# USB_HUB.net
KiCad netlist of a schematic drawn in Altium Designer
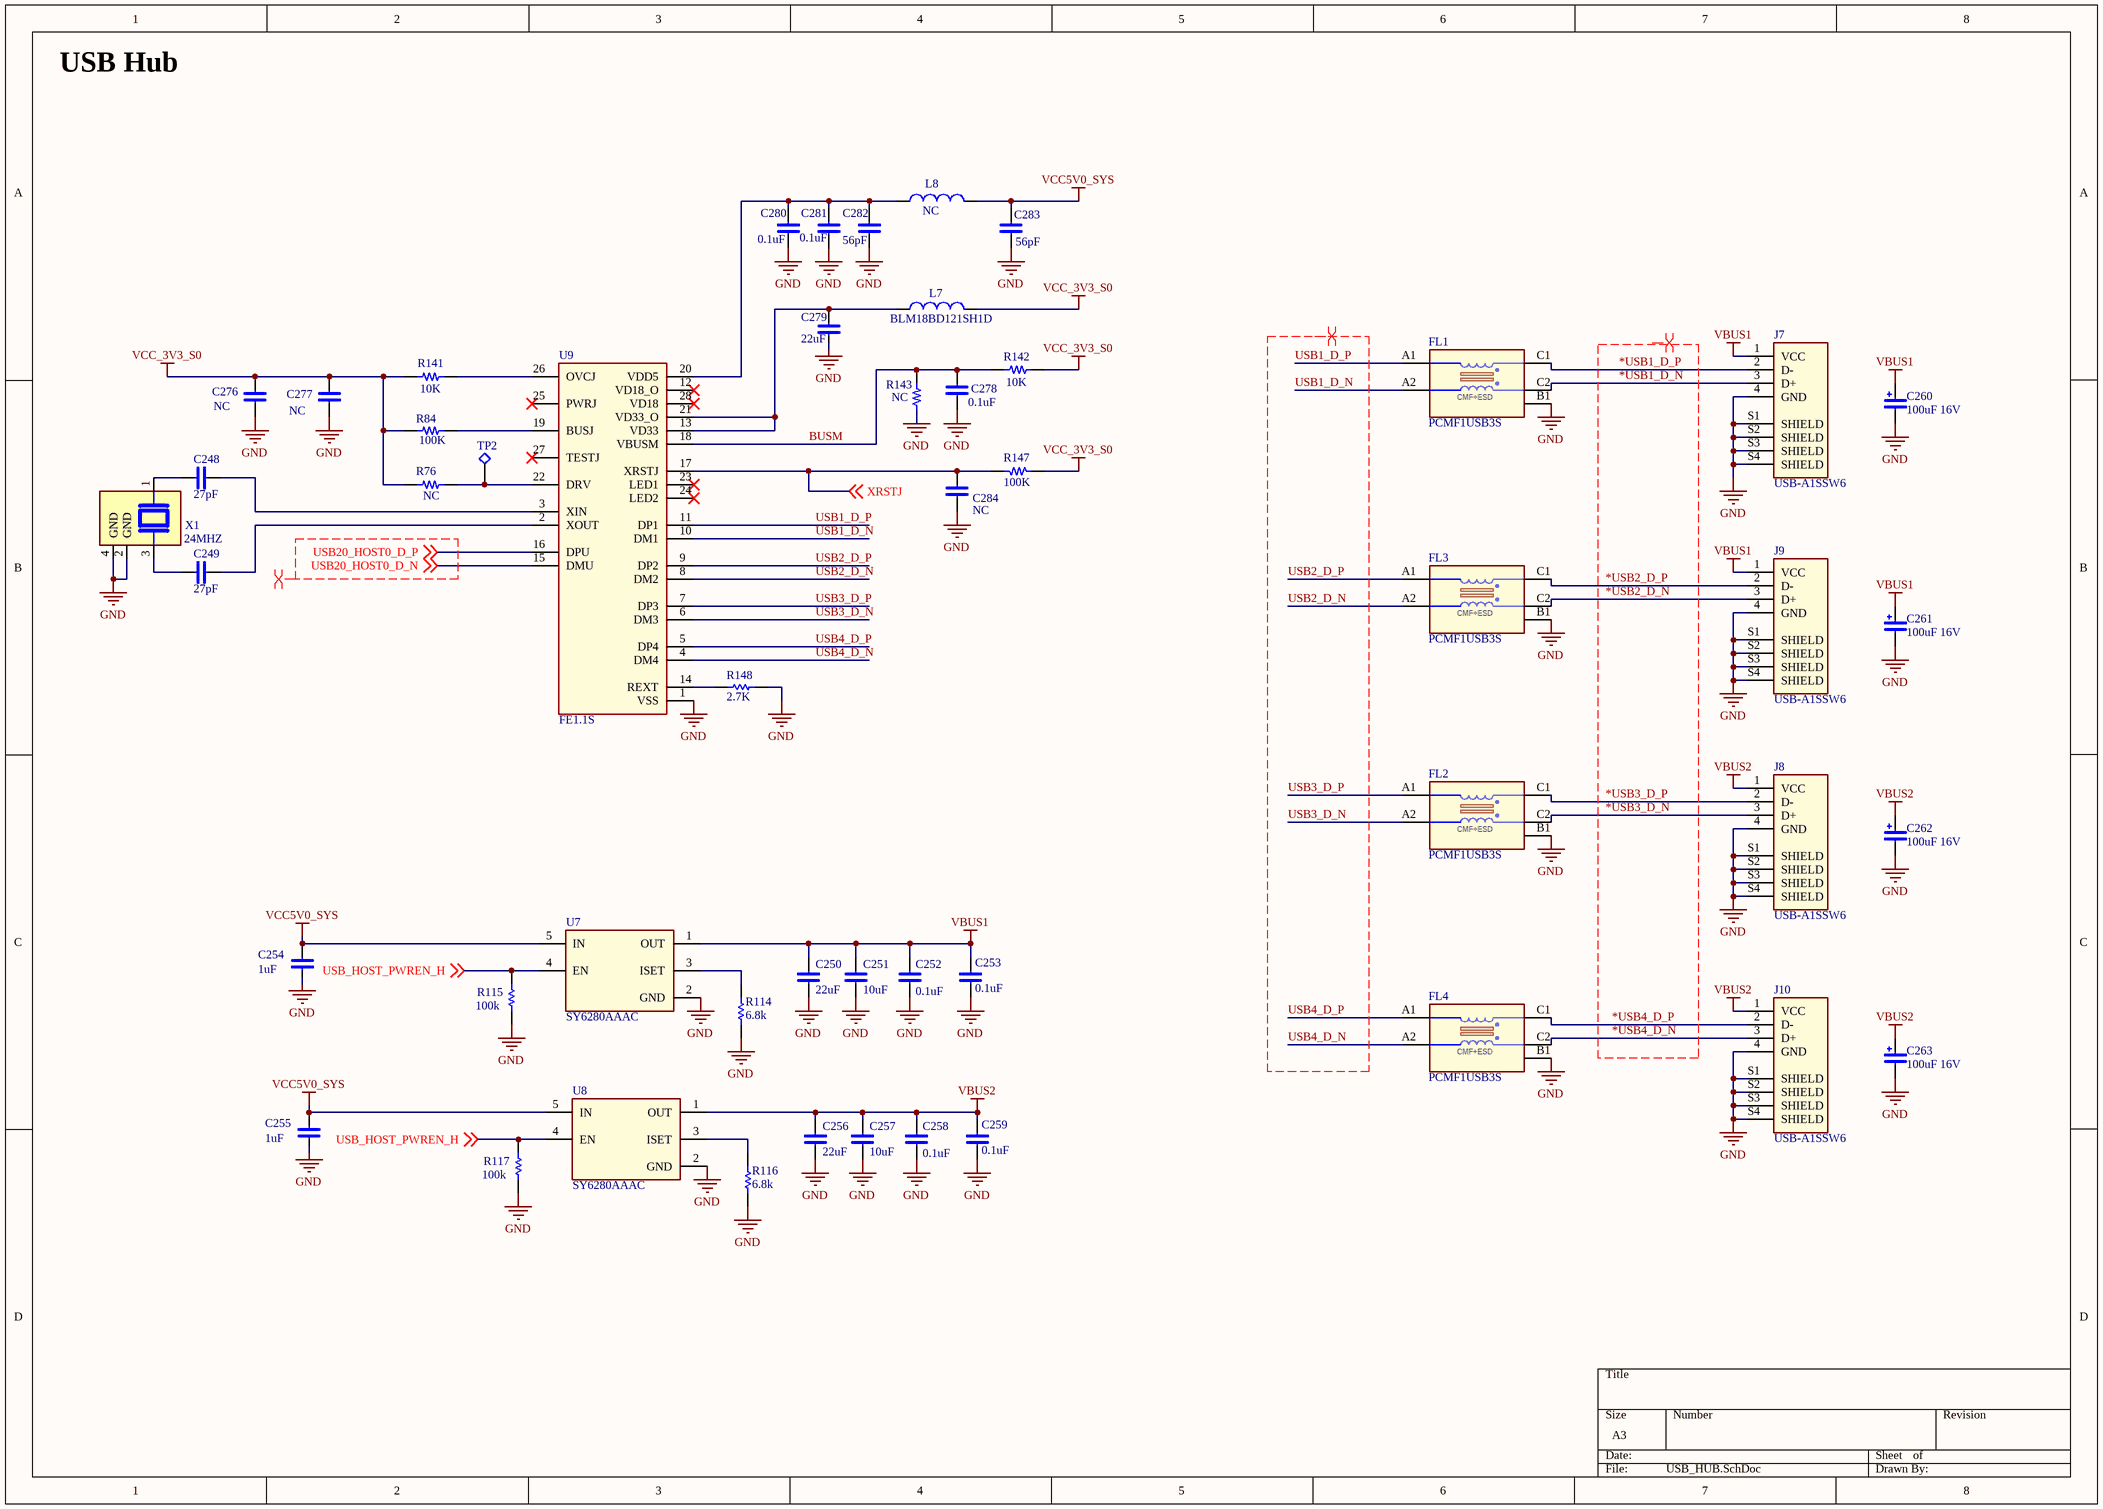
[diagram p0: USB_HUB.SchDoc]

(export (version "E")
  (design (tool "Eeschema 10.0.6"))
  (components
    (comp (ref "C248")
      (value "27pF")
      (footprint "C-0402/1005")
      (description "27pF/50V")
      (fields (field (name "MFR. PART NO.") "GRM21BR71A106KA73K"))
      (libsource (lib "") (part "Capacitor-NonPolar_1"))
    )
    (comp (ref "C249")
      (value "27pF")
      (footprint "C-0402/1005")
      (description "27pF/50V")
      (fields (field (name "MFR. PART NO.") "GRM21BR71A106KA73K"))
      (libsource (lib "Custom_Library") (part "Capacitor-NonPolar"))
    )
    (comp (ref "C250")
      (value "22uF")
      (footprint "C-0603/1608")
      (description "CAP CER 10UF 10V X7R 0805")
      (fields (field (name "MFR. PART NO.") "GRM21BR71A106KA73K"))
      (libsource (lib "Custom_Library") (part "Capacitor-NonPolar"))
    )
    (comp (ref "C251")
      (value "10uF")
      (footprint "C-0603/1608")
      (description "CAP CER 10UF 10V X7R 0805")
      (fields (field (name "MFR. PART NO.") "GRM21BR71A106KA73K"))
      (libsource (lib "Custom_Library") (part "Capacitor-NonPolar"))
    )
    (comp (ref "C252")
      (value "0.1uF")
      (footprint "C-0201/0603")
      (description "0.1uF\r\nC0201")
      (fields (field (name "MFR. PART NO.") "GRM21BR71A106KA73K"))
      (libsource (lib "Custom_Library") (part "Capacitor-NonPolar"))
    )
    (comp (ref "C253")
      (value "0.1uF")
      (footprint "C-0201/0603")
      (description "0.1uF\r\nC0201")
      (fields (field (name "MFR. PART NO.") "GRM21BR71A106KA73K"))
      (libsource (lib "Custom_Library") (part "Capacitor-NonPolar"))
    )
    (comp (ref "C254")
      (value "1uF")
      (footprint "C-0402/1005")
      (description "CAP CER 10UF 10V X7R 0805")
      (fields (field (name "MFR. PART NO.") "GRM21BR71A106KA73K"))
      (libsource (lib "Custom_Library") (part "Capacitor-NonPolar"))
    )
    (comp (ref "C255")
      (value "1uF")
      (footprint "C-0402/1005")
      (description "CAP CER 10UF 10V X7R 0805")
      (fields (field (name "MFR. PART NO.") "GRM21BR71A106KA73K"))
      (libsource (lib "Custom_Library") (part "Capacitor-NonPolar"))
    )
    (comp (ref "C256")
      (value "22uF")
      (footprint "C-0603/1608")
      (description "CAP CER 10UF 10V X7R 0805")
      (fields (field (name "MFR. PART NO.") "GRM21BR71A106KA73K"))
      (libsource (lib "Custom_Library") (part "Capacitor-NonPolar"))
    )
    (comp (ref "C257")
      (value "10uF")
      (footprint "C-0603/1608")
      (description "CAP CER 10UF 10V X7R 0805")
      (fields (field (name "MFR. PART NO.") "GRM21BR71A106KA73K"))
      (libsource (lib "Custom_Library") (part "Capacitor-NonPolar"))
    )
    (comp (ref "C258")
      (value "0.1uF")
      (footprint "C-0201/0603")
      (description "0.1uF\r\nC0201")
      (fields (field (name "MFR. PART NO.") "GRM21BR71A106KA73K"))
      (libsource (lib "Custom_Library") (part "Capacitor-NonPolar"))
    )
    (comp (ref "C259")
      (value "0.1uF")
      (footprint "C-0201/0603")
      (description "0.1uF\r\nC0201")
      (fields (field (name "MFR. PART NO.") "GRM21BR71A106KA73K"))
      (libsource (lib "Custom_Library") (part "Capacitor-NonPolar"))
    )
    (comp (ref "C260")
      (value "100uF 16V")
      (footprint "CAP_2312 TAN")
      (description "CAP TANT 10UF 10% 16V 1206")
      (fields (field (name "MFR. PART NO.") "F931C106KAAAJ6"))
      (libsource (lib "Custom_Library") (part "Capacitor-Polar"))
    )
    (comp (ref "C261")
      (value "100uF 16V")
      (footprint "CAP_2312 TAN")
      (description "CAP TANT 10UF 10% 16V 1206")
      (fields (field (name "MFR. PART NO.") "F931C106KAAAJ6"))
      (libsource (lib "Custom_Library") (part "Capacitor-Polar"))
    )
    (comp (ref "C262")
      (value "100uF 16V")
      (footprint "CAP_2312 TAN")
      (description "CAP TANT 10UF 10% 16V 1206")
      (fields (field (name "MFR. PART NO.") "F931C106KAAAJ6"))
      (libsource (lib "Custom_Library") (part "Capacitor-Polar"))
    )
    (comp (ref "C263")
      (value "100uF 16V")
      (footprint "CAP_2312 TAN")
      (description "CAP TANT 10UF 10% 16V 1206")
      (fields (field (name "MFR. PART NO.") "F931C106KAAAJ6"))
      (libsource (lib "Custom_Library") (part "Capacitor-Polar"))
    )
    (comp (ref "C276")
      (value "NC")
      (footprint "C-0402/1005")
      (description "NC\r\nC0402\r\nX5R")
      (fields (field (name "MFR. PART NO.") "GRM21BR71A106KA73K"))
      (libsource (lib "Custom_Library") (part "Capacitor-NonPolar"))
    )
    (comp (ref "C277")
      (value "NC")
      (footprint "C-0402/1005")
      (description "NC\r\nC0603\r\nX5R")
      (fields (field (name "MFR. PART NO.") "GRM21BR71A106KA73K"))
      (libsource (lib "Custom_Library") (part "Capacitor-NonPolar"))
    )
    (comp (ref "C278")
      (value "0.1uF")
      (footprint "C-0201/0603")
      (description "0.1uF\r\nC0201")
      (fields (field (name "MFR. PART NO.") "GRM21BR71A106KA73K"))
      (libsource (lib "Custom_Library") (part "Capacitor-NonPolar"))
    )
    (comp (ref "C279")
      (value "22uF")
      (footprint "C-0603/1608")
      (description "22uF/10V\r\nC0603")
      (fields (field (name "MFR. PART NO.") "GRM21BR71A106KA73K"))
      (libsource (lib "") (part "Capacitor-NonPolar_1"))
    )
    (comp (ref "C280")
      (value "0.1uF")
      (footprint "C-0201/0603")
      (description "0.1uF\r\nC0201")
      (fields (field (name "MFR. PART NO.") "GRM21BR71A106KA73K"))
      (libsource (lib "Custom_Library") (part "Capacitor-NonPolar"))
    )
    (comp (ref "C281")
      (value "0.1uF")
      (footprint "C-0201/0603")
      (description "0.1uF\r\nC0201")
      (fields (field (name "MFR. PART NO.") "GRM21BR71A106KA73K"))
      (libsource (lib "Custom_Library") (part "Capacitor-NonPolar"))
    )
    (comp (ref "C282")
      (value "56pF")
      (footprint "C-0201/0603")
      (description "56pF/16V")
      (fields (field (name "MFR. PART NO.") "GRM21BR71A106KA73K"))
      (libsource (lib "Custom_Library") (part "Capacitor-NonPolar"))
    )
    (comp (ref "C283")
      (value "56pF")
      (footprint "C-0201/0603")
      (description "56pF/16V")
      (fields (field (name "MFR. PART NO.") "GRM21BR71A106KA73K"))
      (libsource (lib "Custom_Library") (part "Capacitor-NonPolar"))
    )
    (comp (ref "C284")
      (value "NC")
      (footprint "C-0402/1005")
      (description "NC\r\nC0402\r\nX5R")
      (fields (field (name "MFR. PART NO.") "GRM21BR71A106KA73K"))
      (libsource (lib "") (part "Capacitor-NonPolar_1"))
    )
    (comp (ref "FL1")
      (value "PCMF1USB3S")
      (footprint "WLCSP5(2-1-2)_NEX")
      (description "FLT, SMT, WLCSP5, Common Mode EMI Filters")
      (fields (field (name "MANUFACTURER") "Nexperia"))
      (libsource (lib "ZOGX_RK3588_SOC") (part "Nexperia, PCMF1USB3SZ"))
    )
    (comp (ref "FL2")
      (value "PCMF1USB3S")
      (footprint "WLCSP5(2-1-2)_NEX")
      (description "FLT, SMT, WLCSP5, Common Mode EMI Filters")
      (fields (field (name "MANUFACTURER") "Nexperia"))
      (libsource (lib "ZOGX_RK3588_SOC") (part "Nexperia, PCMF1USB3SZ"))
    )
    (comp (ref "FL3")
      (value "PCMF1USB3S")
      (footprint "WLCSP5(2-1-2)_NEX")
      (description "FLT, SMT, WLCSP5, Common Mode EMI Filters")
      (fields (field (name "MANUFACTURER") "Nexperia"))
      (libsource (lib "ZOGX_RK3588_SOC") (part "Nexperia, PCMF1USB3SZ"))
    )
    (comp (ref "FL4")
      (value "PCMF1USB3S")
      (footprint "WLCSP5(2-1-2)_NEX")
      (description "FLT, SMT, WLCSP5, Common Mode EMI Filters")
      (fields (field (name "MANUFACTURER") "Nexperia"))
      (libsource (lib "ZOGX_RK3588_SOC") (part "Nexperia, PCMF1USB3SZ"))
    )
    (comp (ref "J7")
      (value "USB-A1SSW6")
      (footprint "ONSHORE_USB-A1SSW6")
      (description "USB-A (USB TYPE-A) - Receptacle Connector 4 Position Through Hole, Right Angle")
      (fields (field (name "MF") "On Shore"))
      (libsource (lib "ZOGX_RK3588_SOC") (part "USB-A1SSW6"))
    )
    (comp (ref "J8")
      (value "USB-A1SSW6")
      (footprint "ONSHORE_USB-A1SSW6")
      (description "USB-A (USB TYPE-A) - Receptacle Connector 4 Position Through Hole, Right Angle")
      (fields (field (name "MF") "On Shore"))
      (libsource (lib "ZOGX_RK3588_SOC") (part "USB-A1SSW6"))
    )
    (comp (ref "J9")
      (value "USB-A1SSW6")
      (footprint "ONSHORE_USB-A1SSW6")
      (description "USB-A (USB TYPE-A) - Receptacle Connector 4 Position Through Hole, Right Angle")
      (fields (field (name "MF") "On Shore"))
      (libsource (lib "ZOGX_RK3588_SOC") (part "USB-A1SSW6"))
    )
    (comp (ref "J10")
      (value "USB-A1SSW6")
      (footprint "ONSHORE_USB-A1SSW6")
      (description "USB-A (USB TYPE-A) - Receptacle Connector 4 Position Through Hole, Right Angle")
      (fields (field (name "MF") "On Shore"))
      (libsource (lib "ZOGX_RK3588_SOC") (part "USB-A1SSW6"))
    )
    (comp (ref "L7")
      (value "BLM18BD121SH1D")
      (footprint "BEAD_0603")
      (description "Inductor")
      (fields (field (name "PUBLISHER") "Altium Limited"))
      (libsource (lib "Miscellaneous Devices") (part "Inductor"))
    )
    (comp (ref "L8")
      (value "NC")
      (footprint "BEAD_0603")
      (description "Inductor")
      (fields (field (name "PUBLISHER") "Altium Limited"))
      (libsource (lib "Miscellaneous Devices") (part "Inductor"))
    )
    (comp (ref "R76")
      (value "NC")
      (footprint "R-0201/0603")
      (description "1K\r\nR0201")
      (fields (field (name "MFR. PART NO.") "MCR01MZPF1502"))
      (libsource (lib "Custom_Library") (part "Resistor"))
    )
    (comp (ref "R84")
      (value "100K")
      (footprint "R-0201/0603")
      (description "5% R0201 10K")
      (fields (field (name "MFR. PART NO.") "MCR01MZPF1502"))
      (libsource (lib "Custom_Library") (part "Resistor"))
    )
    (comp (ref "R114")
      (value "6.8k")
      (footprint "R-0201/0603")
      (description "2.7K/1% R0201")
      (fields (field (name "PUBLISHER") "Altium Limited"))
      (libsource (lib "Miscellaneous Devices") (part "Res1"))
    )
    (comp (ref "R115")
      (value "100k")
      (footprint "R-0201/0603")
      (description "2.7K/1% R0201")
      (fields (field (name "PUBLISHER") "Altium Limited"))
      (libsource (lib "Miscellaneous Devices") (part "Res1"))
    )
    (comp (ref "R116")
      (value "6.8k")
      (footprint "R-0201/0603")
      (description "2.7K/1% R0201")
      (fields (field (name "PUBLISHER") "Altium Limited"))
      (libsource (lib "Miscellaneous Devices") (part "Res1"))
    )
    (comp (ref "R117")
      (value "100k")
      (footprint "R-0201/0603")
      (description "2.7K/1% R0201")
      (fields (field (name "PUBLISHER") "Altium Limited"))
      (libsource (lib "Miscellaneous Devices") (part "Res1"))
    )
    (comp (ref "R141")
      (value "10K")
      (footprint "R-0201/0603")
      (description "5% R0201 10K")
      (fields (field (name "MFR. PART NO.") "MCR01MZPF1502"))
      (libsource (lib "Custom_Library") (part "Resistor"))
    )
    (comp (ref "R142")
      (value "10K")
      (footprint "R-0201/0603")
      (description "5% R0201 10K")
      (fields (field (name "MFR. PART NO.") "MCR01MZPF1502"))
      (libsource (lib "Custom_Library") (part "Resistor"))
    )
    (comp (ref "R143")
      (value "NC")
      (footprint "R-0201/0603")
      (description "5% R0201 10K")
      (fields (field (name "MFR. PART NO.") "MCR01MZPF1502"))
      (libsource (lib "Custom_Library") (part "Resistor"))
    )
    (comp (ref "R147")
      (value "100K")
      (footprint "R-0201/0603")
      (description "5% R0201 10K")
      (fields (field (name "MFR. PART NO.") "MCR01MZPF1502"))
      (libsource (lib "Custom_Library") (part "Resistor"))
    )
    (comp (ref "R148")
      (value "2.7K")
      (footprint "R-0201/0603")
      (description "2.7K/1% R0201")
      (fields (field (name "PUBLISHER") "Altium Limited"))
      (libsource (lib "Miscellaneous Devices") (part "Res1"))
    )
    (comp (ref "TP2")
      (value "Test Points")
      (footprint "D1.8-H1mm")
      (libsource (lib "Custom_Library") (part "Test Points"))
    )
    (comp (ref "U7")
      (value "SY6280AAAC")
      (footprint "SOT-23-5")
      (libsource (lib "SY6280AAAC") (part "SY6280AAAC"))
    )
    (comp (ref "U8")
      (value "SY6280AAAC")
      (footprint "SOT-23-5")
      (libsource (lib "SY6280AAAC") (part "SY6280AAAC"))
    )
    (comp (ref "U9")
      (value "FE1.1S")
      (footprint "FE1.1S_SSOP-28")
      (description "TSSOP28")
      (fields (field (name "MF") "terminus"))
      (libsource (lib "ZOGX_RK3588_SOC") (part "FE1.1S"))
    )
    (comp (ref "X1")
      (value "24MHZ")
      (footprint "3.2*2.5 CRYSTAL")
      (fields (field (name "MF") "Abracon") (field (name "MP") "ABM8G-25.000MHZ-4Y-T3"))
      (libsource (lib "ABM8G-25.000MHZ-4Y-T3") (part "ABM8G-25.000MHZ-4Y-T3"))
    )
  )
  (nets
    (net (code "1") (name "/*USB1_D_N") (class "Default")
      (node (ref "FL1") (pin "C2") (pinfunction "CH1_OUT-_C2") (pintype "passive"))
      (node (ref "J7") (pin "3") (pinfunction "D+_3") (pintype "passive"))
    )
    (net (code "2") (name "/*USB1_D_P") (class "Default")
      (node (ref "FL1") (pin "C1") (pinfunction "CH1_OUT+_C1") (pintype "passive"))
      (node (ref "J7") (pin "2") (pinfunction "D-_2") (pintype "passive"))
    )
    (net (code "3") (name "/*USB2_D_N") (class "Default")
      (node (ref "FL3") (pin "C2") (pinfunction "CH1_OUT-_C2") (pintype "passive"))
      (node (ref "J9") (pin "3") (pinfunction "D+_3") (pintype "passive"))
    )
    (net (code "4") (name "/*USB2_D_P") (class "Default")
      (node (ref "FL3") (pin "C1") (pinfunction "CH1_OUT+_C1") (pintype "passive"))
      (node (ref "J9") (pin "2") (pinfunction "D-_2") (pintype "passive"))
    )
    (net (code "5") (name "/*USB3_D_N") (class "Default")
      (node (ref "FL2") (pin "C2") (pinfunction "CH1_OUT-_C2") (pintype "passive"))
      (node (ref "J8") (pin "3") (pinfunction "D+_3") (pintype "passive"))
    )
    (net (code "6") (name "/*USB3_D_P") (class "Default")
      (node (ref "FL2") (pin "C1") (pinfunction "CH1_OUT+_C1") (pintype "passive"))
      (node (ref "J8") (pin "2") (pinfunction "D-_2") (pintype "passive"))
    )
    (net (code "7") (name "/*USB4_D_N") (class "Default")
      (node (ref "FL4") (pin "C2") (pinfunction "CH1_OUT-_C2") (pintype "passive"))
      (node (ref "J10") (pin "3") (pinfunction "D+_3") (pintype "passive"))
    )
    (net (code "8") (name "/*USB4_D_P") (class "Default")
      (node (ref "FL4") (pin "C1") (pinfunction "CH1_OUT+_C1") (pintype "passive"))
      (node (ref "J10") (pin "2") (pinfunction "D-_2") (pintype "passive"))
    )
    (net (code "9") (name "/BUSM") (class "Default")
      (node (ref "C278") (pin "1") (pinfunction "1_1") (pintype "passive"))
      (node (ref "R142") (pin "2") (pinfunction "2_2") (pintype "passive"))
      (node (ref "R143") (pin "1") (pinfunction "1_1") (pintype "passive"))
      (node (ref "U9") (pin "18") (pinfunction "VBUSM_18") (pintype "passive"))
    )
    (net (code "10") (name "/USB1_D_N") (class "Default")
      (node (ref "FL1") (pin "A2") (pinfunction "CH1_IN-_A2") (pintype "passive"))
      (node (ref "U9") (pin "10") (pinfunction "DM1_10") (pintype "passive"))
    )
    (net (code "11") (name "/USB1_D_P") (class "Default")
      (node (ref "FL1") (pin "A1") (pinfunction "CH1_IN+_A1") (pintype "passive"))
      (node (ref "U9") (pin "11") (pinfunction "DP1_11") (pintype "passive"))
    )
    (net (code "12") (name "/USB2_D_N") (class "Default")
      (node (ref "FL3") (pin "A2") (pinfunction "CH1_IN-_A2") (pintype "passive"))
      (node (ref "U9") (pin "8") (pinfunction "DM2_8") (pintype "passive"))
    )
    (net (code "13") (name "/USB2_D_P") (class "Default")
      (node (ref "FL3") (pin "A1") (pinfunction "CH1_IN+_A1") (pintype "passive"))
      (node (ref "U9") (pin "9") (pinfunction "DP2_9") (pintype "passive"))
    )
    (net (code "14") (name "/USB3_D_N") (class "Default")
      (node (ref "FL2") (pin "A2") (pinfunction "CH1_IN-_A2") (pintype "passive"))
      (node (ref "U9") (pin "6") (pinfunction "DM3_6") (pintype "passive"))
    )
    (net (code "15") (name "/USB3_D_P") (class "Default")
      (node (ref "FL2") (pin "A1") (pinfunction "CH1_IN+_A1") (pintype "passive"))
      (node (ref "U9") (pin "7") (pinfunction "DP3_7") (pintype "passive"))
    )
    (net (code "16") (name "/USB4_D_N") (class "Default")
      (node (ref "FL4") (pin "A2") (pinfunction "CH1_IN-_A2") (pintype "passive"))
      (node (ref "U9") (pin "4") (pinfunction "DM4_4") (pintype "passive"))
    )
    (net (code "17") (name "/USB4_D_P") (class "Default")
      (node (ref "FL4") (pin "A1") (pinfunction "CH1_IN+_A1") (pintype "passive"))
      (node (ref "U9") (pin "5") (pinfunction "DP4_5") (pintype "passive"))
    )
    (net (code "18") (name "GND") (class "Default")
      (node (ref "C250") (pin "2") (pinfunction "2_2") (pintype "passive"))
      (node (ref "C251") (pin "2") (pinfunction "2_2") (pintype "passive"))
      (node (ref "C252") (pin "2") (pinfunction "2_2") (pintype "passive"))
      (node (ref "C253") (pin "2") (pinfunction "2_2") (pintype "passive"))
      (node (ref "C254") (pin "2") (pinfunction "2_2") (pintype "passive"))
      (node (ref "C255") (pin "2") (pinfunction "2_2") (pintype "passive"))
      (node (ref "C256") (pin "2") (pinfunction "2_2") (pintype "passive"))
      (node (ref "C257") (pin "2") (pinfunction "2_2") (pintype "passive"))
      (node (ref "C258") (pin "2") (pinfunction "2_2") (pintype "passive"))
      (node (ref "C259") (pin "2") (pinfunction "2_2") (pintype "passive"))
      (node (ref "C260") (pin "-") (pinfunction "-_-") (pintype "passive"))
      (node (ref "C261") (pin "-") (pinfunction "-_-") (pintype "passive"))
      (node (ref "C262") (pin "-") (pinfunction "-_-") (pintype "passive"))
      (node (ref "C263") (pin "-") (pinfunction "-_-") (pintype "passive"))
      (node (ref "C276") (pin "2") (pinfunction "2_2") (pintype "passive"))
      (node (ref "C277") (pin "2") (pinfunction "2_2") (pintype "passive"))
      (node (ref "C278") (pin "2") (pinfunction "2_2") (pintype "passive"))
      (node (ref "C279") (pin "2") (pinfunction "2_2") (pintype "passive"))
      (node (ref "C280") (pin "2") (pinfunction "2_2") (pintype "passive"))
      (node (ref "C281") (pin "2") (pinfunction "2_2") (pintype "passive"))
      (node (ref "C282") (pin "2") (pinfunction "2_2") (pintype "passive"))
      (node (ref "C283") (pin "2") (pinfunction "2_2") (pintype "passive"))
      (node (ref "C284") (pin "2") (pinfunction "2_2") (pintype "passive"))
      (node (ref "FL1") (pin "B1") (pinfunction "GND_B1") (pintype "power_in"))
      (node (ref "FL2") (pin "B1") (pinfunction "GND_B1") (pintype "power_in"))
      (node (ref "FL3") (pin "B1") (pinfunction "GND_B1") (pintype "power_in"))
      (node (ref "FL4") (pin "B1") (pinfunction "GND_B1") (pintype "power_in"))
      (node (ref "J10") (pin "4") (pinfunction "GND_4") (pintype "passive"))
      (node (ref "J10") (pin "S1") (pinfunction "SHIELD_S1") (pintype "passive"))
      (node (ref "J10") (pin "S2") (pinfunction "SHIELD_S2") (pintype "passive"))
      (node (ref "J10") (pin "S3") (pinfunction "SHIELD_S3") (pintype "passive"))
      (node (ref "J10") (pin "S4") (pinfunction "SHIELD_S4") (pintype "passive"))
      (node (ref "J7") (pin "4") (pinfunction "GND_4") (pintype "passive"))
      (node (ref "J7") (pin "S1") (pinfunction "SHIELD_S1") (pintype "passive"))
      (node (ref "J7") (pin "S2") (pinfunction "SHIELD_S2") (pintype "passive"))
      (node (ref "J7") (pin "S3") (pinfunction "SHIELD_S3") (pintype "passive"))
      (node (ref "J7") (pin "S4") (pinfunction "SHIELD_S4") (pintype "passive"))
      (node (ref "J8") (pin "4") (pinfunction "GND_4") (pintype "passive"))
      (node (ref "J8") (pin "S1") (pinfunction "SHIELD_S1") (pintype "passive"))
      (node (ref "J8") (pin "S2") (pinfunction "SHIELD_S2") (pintype "passive"))
      (node (ref "J8") (pin "S3") (pinfunction "SHIELD_S3") (pintype "passive"))
      (node (ref "J8") (pin "S4") (pinfunction "SHIELD_S4") (pintype "passive"))
      (node (ref "J9") (pin "4") (pinfunction "GND_4") (pintype "passive"))
      (node (ref "J9") (pin "S1") (pinfunction "SHIELD_S1") (pintype "passive"))
      (node (ref "J9") (pin "S2") (pinfunction "SHIELD_S2") (pintype "passive"))
      (node (ref "J9") (pin "S3") (pinfunction "SHIELD_S3") (pintype "passive"))
      (node (ref "J9") (pin "S4") (pinfunction "SHIELD_S4") (pintype "passive"))
      (node (ref "R114") (pin "1") (pinfunction "1_1") (pintype "passive"))
      (node (ref "R115") (pin "1") (pinfunction "1_1") (pintype "passive"))
      (node (ref "R116") (pin "1") (pinfunction "1_1") (pintype "passive"))
      (node (ref "R117") (pin "1") (pinfunction "1_1") (pintype "passive"))
      (node (ref "R143") (pin "2") (pinfunction "2_2") (pintype "passive"))
      (node (ref "R148") (pin "2") (pinfunction "2_2") (pintype "passive"))
      (node (ref "U7") (pin "2") (pinfunction "GND_2") (pintype "passive"))
      (node (ref "U8") (pin "2") (pinfunction "GND_2") (pintype "passive"))
      (node (ref "U9") (pin "1") (pinfunction "VSS_1") (pintype "passive"))
      (node (ref "X1") (pin "2") (pinfunction "GND_2") (pintype "power_in"))
      (node (ref "X1") (pin "4") (pinfunction "GND_4") (pintype "power_in"))
    )
    (net (code "19") (name "Net-(C248-Pad2)") (class "Default")
      (node (ref "C248") (pin "2") (pinfunction "2_2") (pintype "passive"))
      (node (ref "X1") (pin "1") (pinfunction "1_1") (pintype "passive"))
    )
    (net (code "20") (name "Net-(U7-ISET)") (class "Default")
      (node (ref "R114") (pin "2") (pinfunction "2_2") (pintype "passive"))
      (node (ref "U7") (pin "3") (pinfunction "ISET_3") (pintype "passive"))
    )
    (net (code "21") (name "Net-(U8-ISET)") (class "Default")
      (node (ref "R116") (pin "2") (pinfunction "2_2") (pintype "passive"))
      (node (ref "U8") (pin "3") (pinfunction "ISET_3") (pintype "passive"))
    )
    (net (code "22") (name "Net-(U9-BUSJ)") (class "Default")
      (node (ref "R84") (pin "1") (pinfunction "1_1") (pintype "passive"))
      (node (ref "U9") (pin "19") (pinfunction "BUSJ_19") (pintype "passive"))
    )
    (net (code "23") (name "Net-(U9-DRV)") (class "Default")
      (node (ref "R76") (pin "2") (pinfunction "2_2") (pintype "passive"))
      (node (ref "TP2") (pin "1") (pinfunction "1_1") (pintype "passive"))
      (node (ref "U9") (pin "22") (pinfunction "DRV_22") (pintype "passive"))
    )
    (net (code "24") (name "Net-(U9-OVCJ)") (class "Default")
      (node (ref "R141") (pin "1") (pinfunction "1_1") (pintype "passive"))
      (node (ref "U9") (pin "26") (pinfunction "OVCJ_26") (pintype "passive"))
    )
    (net (code "25") (name "Net-(U9-REXT)") (class "Default")
      (node (ref "R148") (pin "1") (pinfunction "1_1") (pintype "passive"))
      (node (ref "U9") (pin "14") (pinfunction "REXT_14") (pintype "passive"))
    )
    (net (code "26") (name "Net-(U9-VD33)") (class "Default")
      (node (ref "C279") (pin "1") (pinfunction "1_1") (pintype "passive"))
      (node (ref "L7") (pin "2") (pinfunction "2_2") (pintype "passive"))
      (node (ref "U9") (pin "13") (pinfunction "VD33_13") (pintype "passive"))
      (node (ref "U9") (pin "21") (pinfunction "VD33_O_21") (pintype "passive"))
    )
    (net (code "27") (name "Net-(U9-VDD5)") (class "Default")
      (node (ref "C280") (pin "1") (pinfunction "1_1") (pintype "passive"))
      (node (ref "C281") (pin "1") (pinfunction "1_1") (pintype "passive"))
      (node (ref "C282") (pin "1") (pinfunction "1_1") (pintype "passive"))
      (node (ref "L8") (pin "2") (pinfunction "2_2") (pintype "passive"))
      (node (ref "U9") (pin "20") (pinfunction "VDD5_20") (pintype "passive"))
    )
    (net (code "28") (name "Net-(U9-XIN)") (class "Default")
      (node (ref "C248") (pin "1") (pinfunction "1_1") (pintype "passive"))
      (node (ref "U9") (pin "3") (pinfunction "XIN_3") (pintype "passive"))
    )
    (net (code "29") (name "Net-(U9-XOUT)") (class "Default")
      (node (ref "C249") (pin "1") (pinfunction "1_1") (pintype "passive"))
      (node (ref "U9") (pin "2") (pinfunction "XOUT_2") (pintype "passive"))
    )
    (net (code "30") (name "Net-(X1-2)") (class "Default")
      (node (ref "C249") (pin "2") (pinfunction "2_2") (pintype "passive"))
      (node (ref "X1") (pin "3") (pinfunction "2_3") (pintype "passive"))
    )
    (net (code "31") (name "USB20_HOST0_D_N") (class "Default")
      (node (ref "U9") (pin "15") (pinfunction "DMU_15") (pintype "passive"))
    )
    (net (code "32") (name "USB20_HOST0_D_P") (class "Default")
      (node (ref "U9") (pin "16") (pinfunction "DPU_16") (pintype "passive"))
    )
    (net (code "33") (name "USB_HOST_PWREN_H") (class "Default")
      (node (ref "R115") (pin "2") (pinfunction "2_2") (pintype "passive"))
      (node (ref "R117") (pin "2") (pinfunction "2_2") (pintype "passive"))
      (node (ref "U7") (pin "4") (pinfunction "EN_4") (pintype "passive"))
      (node (ref "U8") (pin "4") (pinfunction "EN_4") (pintype "passive"))
    )
    (net (code "34") (name "VBUS1") (class "Default")
      (node (ref "C250") (pin "1") (pinfunction "1_1") (pintype "passive"))
      (node (ref "C251") (pin "1") (pinfunction "1_1") (pintype "passive"))
      (node (ref "C252") (pin "1") (pinfunction "1_1") (pintype "passive"))
      (node (ref "C253") (pin "1") (pinfunction "1_1") (pintype "passive"))
      (node (ref "C260") (pin "+") (pinfunction "+_+") (pintype "passive"))
      (node (ref "C261") (pin "+") (pinfunction "+_+") (pintype "passive"))
      (node (ref "J7") (pin "1") (pinfunction "VCC_1") (pintype "passive"))
      (node (ref "J9") (pin "1") (pinfunction "VCC_1") (pintype "passive"))
      (node (ref "U7") (pin "1") (pinfunction "OUT_1") (pintype "passive"))
    )
    (net (code "35") (name "VBUS2") (class "Default")
      (node (ref "C256") (pin "1") (pinfunction "1_1") (pintype "passive"))
      (node (ref "C257") (pin "1") (pinfunction "1_1") (pintype "passive"))
      (node (ref "C258") (pin "1") (pinfunction "1_1") (pintype "passive"))
      (node (ref "C259") (pin "1") (pinfunction "1_1") (pintype "passive"))
      (node (ref "C262") (pin "+") (pinfunction "+_+") (pintype "passive"))
      (node (ref "C263") (pin "+") (pinfunction "+_+") (pintype "passive"))
      (node (ref "J10") (pin "1") (pinfunction "VCC_1") (pintype "passive"))
      (node (ref "J8") (pin "1") (pinfunction "VCC_1") (pintype "passive"))
      (node (ref "U8") (pin "1") (pinfunction "OUT_1") (pintype "passive"))
    )
    (net (code "36") (name "VCC5V0_SYS") (class "Default")
      (node (ref "C254") (pin "1") (pinfunction "1_1") (pintype "passive"))
      (node (ref "C255") (pin "1") (pinfunction "1_1") (pintype "passive"))
      (node (ref "C283") (pin "1") (pinfunction "1_1") (pintype "passive"))
      (node (ref "L8") (pin "1") (pinfunction "1_1") (pintype "passive"))
      (node (ref "U7") (pin "5") (pinfunction "IN_5") (pintype "passive"))
      (node (ref "U8") (pin "5") (pinfunction "IN_5") (pintype "passive"))
    )
    (net (code "37") (name "VCC_3V3_S0") (class "Default")
      (node (ref "C276") (pin "1") (pinfunction "1_1") (pintype "passive"))
      (node (ref "C277") (pin "1") (pinfunction "1_1") (pintype "passive"))
      (node (ref "L7") (pin "1") (pinfunction "1_1") (pintype "passive"))
      (node (ref "R141") (pin "2") (pinfunction "2_2") (pintype "passive"))
      (node (ref "R142") (pin "1") (pinfunction "1_1") (pintype "passive"))
      (node (ref "R147") (pin "1") (pinfunction "1_1") (pintype "passive"))
      (node (ref "R76") (pin "1") (pinfunction "1_1") (pintype "passive"))
      (node (ref "R84") (pin "2") (pinfunction "2_2") (pintype "passive"))
    )
    (net (code "38") (name "XRSTJ") (class "Default")
      (node (ref "C284") (pin "1") (pinfunction "1_1") (pintype "passive"))
      (node (ref "R147") (pin "2") (pinfunction "2_2") (pintype "passive"))
      (node (ref "U9") (pin "17") (pinfunction "XRSTJ_17") (pintype "passive"))
    )
    (net (code "39") (name "unconnected-(U9-LED1-Pad23)") (class "Default")
      (node (ref "U9") (pin "23") (pinfunction "LED1_23") (pintype "passive+no_connect"))
    )
    (net (code "40") (name "unconnected-(U9-LED2-Pad24)") (class "Default")
      (node (ref "U9") (pin "24") (pinfunction "LED2_24") (pintype "passive+no_connect"))
    )
    (net (code "41") (name "unconnected-(U9-PWRJ-Pad25)") (class "Default")
      (node (ref "U9") (pin "25") (pinfunction "PWRJ_25") (pintype "passive+no_connect"))
    )
    (net (code "42") (name "unconnected-(U9-TESTJ-Pad27)") (class "Default")
      (node (ref "U9") (pin "27") (pinfunction "TESTJ_27") (pintype "passive+no_connect"))
    )
    (net (code "43") (name "unconnected-(U9-VD18-Pad28)") (class "Default")
      (node (ref "U9") (pin "28") (pinfunction "VD18_28") (pintype "passive+no_connect"))
    )
    (net (code "44") (name "unconnected-(U9-VD18_O-Pad12)") (class "Default")
      (node (ref "U9") (pin "12") (pinfunction "VD18_O_12") (pintype "passive+no_connect"))
    )
  )
)
